# pin_conditiong.net
KiCad netlist of a schematic drawn in Altium Designer
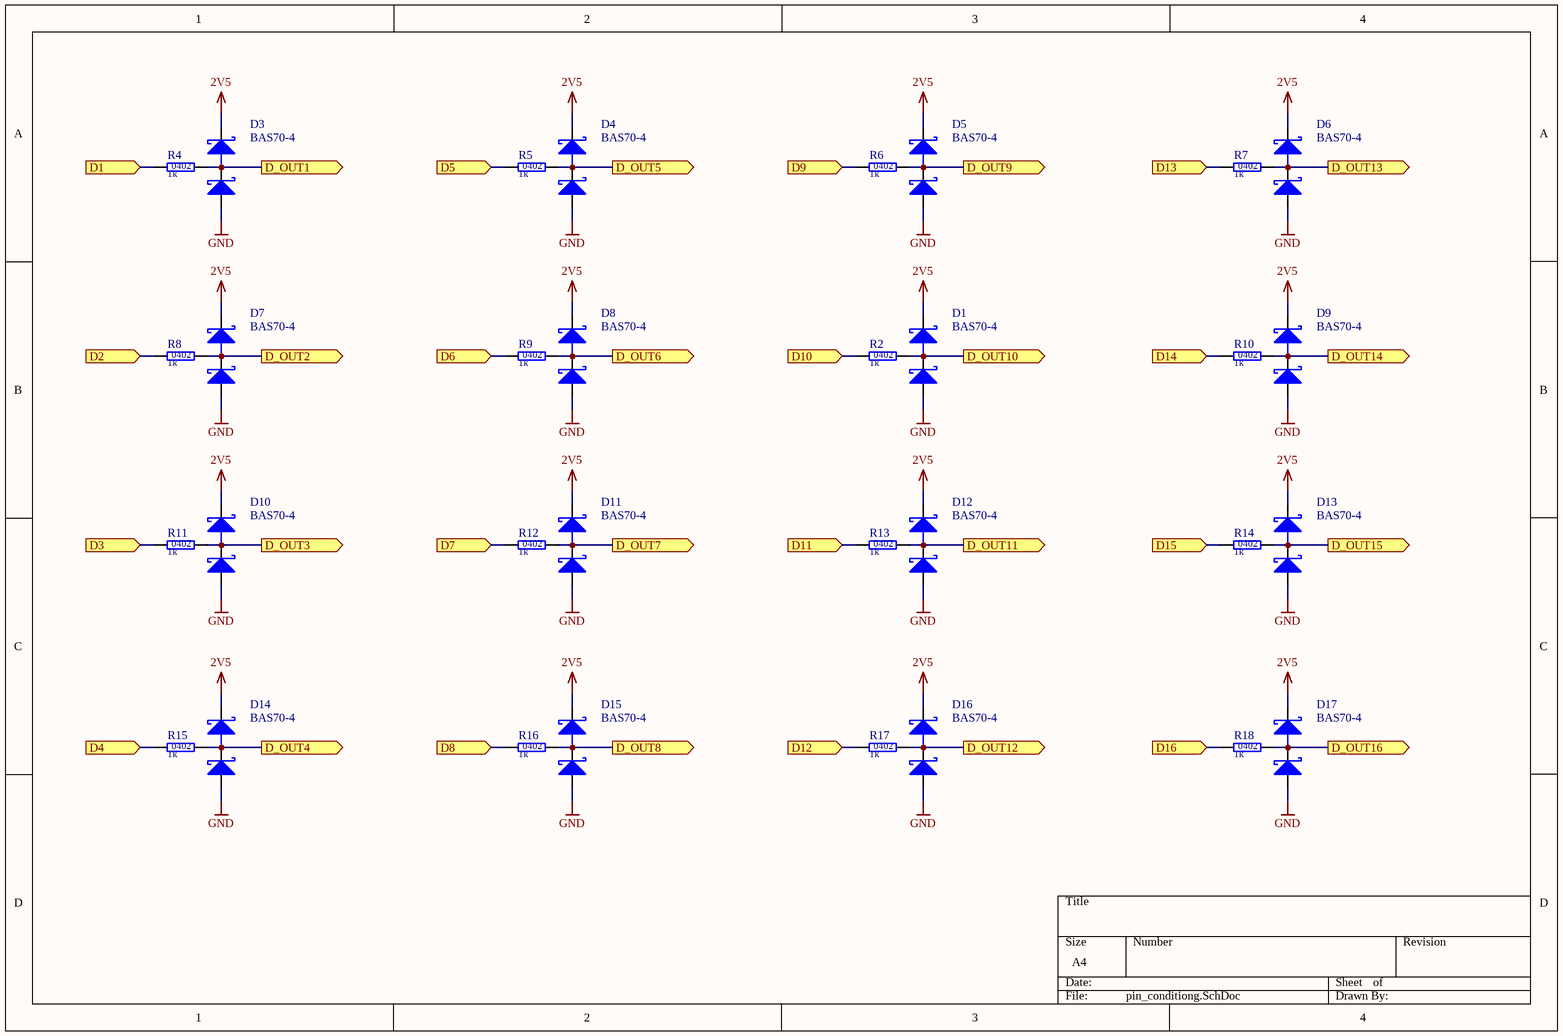
[diagram p0: pin_conditiong.SchDoc]

(export (version "E")
  (design (tool "Eeschema 10.0.6"))
  (components
    (comp (ref "D1")
      (value "BAS70-4")
      (footprint "BAS70-4")
      (description "Dioda: prostownicza Schottky; SMD; 70V; 70mA; 5ns; SOT23; 200mW")
      (libsource (lib "soldering_station") (part "BAS70-4"))
    )
    (comp (ref "D3")
      (value "BAS70-4")
      (footprint "BAS70-4")
      (description "Dioda: prostownicza Schottky; SMD; 70V; 70mA; 5ns; SOT23; 200mW")
      (libsource (lib "soldering_station") (part "BAS70-4"))
    )
    (comp (ref "D4")
      (value "BAS70-4")
      (footprint "BAS70-4")
      (description "Dioda: prostownicza Schottky; SMD; 70V; 70mA; 5ns; SOT23; 200mW")
      (libsource (lib "soldering_station") (part "BAS70-4"))
    )
    (comp (ref "D5")
      (value "BAS70-4")
      (footprint "BAS70-4")
      (description "Dioda: prostownicza Schottky; SMD; 70V; 70mA; 5ns; SOT23; 200mW")
      (libsource (lib "soldering_station") (part "BAS70-4"))
    )
    (comp (ref "D6")
      (value "BAS70-4")
      (footprint "BAS70-4")
      (description "Dioda: prostownicza Schottky; SMD; 70V; 70mA; 5ns; SOT23; 200mW")
      (libsource (lib "soldering_station") (part "BAS70-4"))
    )
    (comp (ref "D7")
      (value "BAS70-4")
      (footprint "BAS70-4")
      (description "Dioda: prostownicza Schottky; SMD; 70V; 70mA; 5ns; SOT23; 200mW")
      (libsource (lib "soldering_station") (part "BAS70-4"))
    )
    (comp (ref "D8")
      (value "BAS70-4")
      (footprint "BAS70-4")
      (description "Dioda: prostownicza Schottky; SMD; 70V; 70mA; 5ns; SOT23; 200mW")
      (libsource (lib "soldering_station") (part "BAS70-4"))
    )
    (comp (ref "D9")
      (value "BAS70-4")
      (footprint "BAS70-4")
      (description "Dioda: prostownicza Schottky; SMD; 70V; 70mA; 5ns; SOT23; 200mW")
      (libsource (lib "soldering_station") (part "BAS70-4"))
    )
    (comp (ref "D10")
      (value "BAS70-4")
      (footprint "BAS70-4")
      (description "Dioda: prostownicza Schottky; SMD; 70V; 70mA; 5ns; SOT23; 200mW")
      (libsource (lib "soldering_station") (part "BAS70-4"))
    )
    (comp (ref "D11")
      (value "BAS70-4")
      (footprint "BAS70-4")
      (description "Dioda: prostownicza Schottky; SMD; 70V; 70mA; 5ns; SOT23; 200mW")
      (libsource (lib "soldering_station") (part "BAS70-4"))
    )
    (comp (ref "D12")
      (value "BAS70-4")
      (footprint "BAS70-4")
      (description "Dioda: prostownicza Schottky; SMD; 70V; 70mA; 5ns; SOT23; 200mW")
      (libsource (lib "soldering_station") (part "BAS70-4"))
    )
    (comp (ref "D13")
      (value "BAS70-4")
      (footprint "BAS70-4")
      (description "Dioda: prostownicza Schottky; SMD; 70V; 70mA; 5ns; SOT23; 200mW")
      (libsource (lib "soldering_station") (part "BAS70-4"))
    )
    (comp (ref "D14")
      (value "BAS70-4")
      (footprint "BAS70-4")
      (description "Dioda: prostownicza Schottky; SMD; 70V; 70mA; 5ns; SOT23; 200mW")
      (libsource (lib "soldering_station") (part "BAS70-4"))
    )
    (comp (ref "D15")
      (value "BAS70-4")
      (footprint "BAS70-4")
      (description "Dioda: prostownicza Schottky; SMD; 70V; 70mA; 5ns; SOT23; 200mW")
      (libsource (lib "soldering_station") (part "BAS70-4"))
    )
    (comp (ref "D16")
      (value "BAS70-4")
      (footprint "BAS70-4")
      (description "Dioda: prostownicza Schottky; SMD; 70V; 70mA; 5ns; SOT23; 200mW")
      (libsource (lib "soldering_station") (part "BAS70-4"))
    )
    (comp (ref "D17")
      (value "BAS70-4")
      (footprint "BAS70-4")
      (description "Dioda: prostownicza Schottky; SMD; 70V; 70mA; 5ns; SOT23; 200mW")
      (libsource (lib "soldering_station") (part "BAS70-4"))
    )
    (comp (ref "R2")
      (value "1k")
      (footprint "R_0402_1005")
      (fields
        (field (name "SCH_FOOTPRINT") "0402")
        (field (name "PART NUMBER") "R_1k_0402_1")
        (field (name "VOLTAGE") "50V")
        (field (name "POWER") "63mW")
      )
      (libsource (lib "Library") (part "R"))
    )
    (comp (ref "R4")
      (value "1k")
      (footprint "R_0402_1005")
      (fields
        (field (name "SCH_FOOTPRINT") "0402")
        (field (name "PART NUMBER") "R_1k_0402_1")
        (field (name "VOLTAGE") "50V")
        (field (name "POWER") "63mW")
      )
      (libsource (lib "Library") (part "R"))
    )
    (comp (ref "R5")
      (value "1k")
      (footprint "R_0402_1005")
      (fields
        (field (name "SCH_FOOTPRINT") "0402")
        (field (name "PART NUMBER") "R_1k_0402_1")
        (field (name "VOLTAGE") "50V")
        (field (name "POWER") "63mW")
      )
      (libsource (lib "Library") (part "R"))
    )
    (comp (ref "R6")
      (value "1k")
      (footprint "R_0402_1005")
      (fields
        (field (name "SCH_FOOTPRINT") "0402")
        (field (name "PART NUMBER") "R_1k_0402_1")
        (field (name "VOLTAGE") "50V")
        (field (name "POWER") "63mW")
      )
      (libsource (lib "Library") (part "R"))
    )
    (comp (ref "R7")
      (value "1k")
      (footprint "R_0402_1005")
      (fields
        (field (name "SCH_FOOTPRINT") "0402")
        (field (name "PART NUMBER") "R_1k_0402_1")
        (field (name "VOLTAGE") "50V")
        (field (name "POWER") "63mW")
      )
      (libsource (lib "Library") (part "R"))
    )
    (comp (ref "R8")
      (value "1k")
      (footprint "R_0402_1005")
      (fields
        (field (name "SCH_FOOTPRINT") "0402")
        (field (name "PART NUMBER") "R_1k_0402_1")
        (field (name "VOLTAGE") "50V")
        (field (name "POWER") "63mW")
      )
      (libsource (lib "Library") (part "R"))
    )
    (comp (ref "R9")
      (value "1k")
      (footprint "R_0402_1005")
      (fields
        (field (name "SCH_FOOTPRINT") "0402")
        (field (name "PART NUMBER") "R_1k_0402_1")
        (field (name "VOLTAGE") "50V")
        (field (name "POWER") "63mW")
      )
      (libsource (lib "Library") (part "R"))
    )
    (comp (ref "R10")
      (value "1k")
      (footprint "R_0402_1005")
      (fields
        (field (name "SCH_FOOTPRINT") "0402")
        (field (name "PART NUMBER") "R_1k_0402_1")
        (field (name "VOLTAGE") "50V")
        (field (name "POWER") "63mW")
      )
      (libsource (lib "Library") (part "R"))
    )
    (comp (ref "R11")
      (value "1k")
      (footprint "R_0402_1005")
      (fields
        (field (name "SCH_FOOTPRINT") "0402")
        (field (name "PART NUMBER") "R_1k_0402_1")
        (field (name "VOLTAGE") "50V")
        (field (name "POWER") "63mW")
      )
      (libsource (lib "Library") (part "R"))
    )
    (comp (ref "R12")
      (value "1k")
      (footprint "R_0402_1005")
      (fields
        (field (name "SCH_FOOTPRINT") "0402")
        (field (name "PART NUMBER") "R_1k_0402_1")
        (field (name "VOLTAGE") "50V")
        (field (name "POWER") "63mW")
      )
      (libsource (lib "Library") (part "R"))
    )
    (comp (ref "R13")
      (value "1k")
      (footprint "R_0402_1005")
      (fields
        (field (name "SCH_FOOTPRINT") "0402")
        (field (name "PART NUMBER") "R_1k_0402_1")
        (field (name "VOLTAGE") "50V")
        (field (name "POWER") "63mW")
      )
      (libsource (lib "Library") (part "R"))
    )
    (comp (ref "R14")
      (value "1k")
      (footprint "R_0402_1005")
      (fields
        (field (name "SCH_FOOTPRINT") "0402")
        (field (name "PART NUMBER") "R_1k_0402_1")
        (field (name "VOLTAGE") "50V")
        (field (name "POWER") "63mW")
      )
      (libsource (lib "Library") (part "R"))
    )
    (comp (ref "R15")
      (value "1k")
      (footprint "R_0402_1005")
      (fields
        (field (name "SCH_FOOTPRINT") "0402")
        (field (name "PART NUMBER") "R_1k_0402_1")
        (field (name "VOLTAGE") "50V")
        (field (name "POWER") "63mW")
      )
      (libsource (lib "Library") (part "R"))
    )
    (comp (ref "R16")
      (value "1k")
      (footprint "R_0402_1005")
      (fields
        (field (name "SCH_FOOTPRINT") "0402")
        (field (name "PART NUMBER") "R_1k_0402_1")
        (field (name "VOLTAGE") "50V")
        (field (name "POWER") "63mW")
      )
      (libsource (lib "Library") (part "R"))
    )
    (comp (ref "R17")
      (value "1k")
      (footprint "R_0402_1005")
      (fields
        (field (name "SCH_FOOTPRINT") "0402")
        (field (name "PART NUMBER") "R_1k_0402_1")
        (field (name "VOLTAGE") "50V")
        (field (name "POWER") "63mW")
      )
      (libsource (lib "Library") (part "R"))
    )
    (comp (ref "R18")
      (value "1k")
      (footprint "R_0402_1005")
      (fields
        (field (name "SCH_FOOTPRINT") "0402")
        (field (name "PART NUMBER") "R_1k_0402_1")
        (field (name "VOLTAGE") "50V")
        (field (name "POWER") "63mW")
      )
      (libsource (lib "Library") (part "R"))
    )
  )
  (nets
    (net (code "1") (name "/D1") (class "Default")
      (node (ref "R4") (pin "1") (pinfunction "1_1") (pintype "passive"))
    )
    (net (code "2") (name "/D2") (class "Default")
      (node (ref "R8") (pin "1") (pinfunction "1_1") (pintype "passive"))
    )
    (net (code "3") (name "/D3") (class "Default")
      (node (ref "R11") (pin "1") (pinfunction "1_1") (pintype "passive"))
    )
    (net (code "4") (name "/D4") (class "Default")
      (node (ref "R15") (pin "1") (pinfunction "1_1") (pintype "passive"))
    )
    (net (code "5") (name "/D5") (class "Default")
      (node (ref "R5") (pin "1") (pinfunction "1_1") (pintype "passive"))
    )
    (net (code "6") (name "/D6") (class "Default")
      (node (ref "R9") (pin "1") (pinfunction "1_1") (pintype "passive"))
    )
    (net (code "7") (name "/D7") (class "Default")
      (node (ref "R12") (pin "1") (pinfunction "1_1") (pintype "passive"))
    )
    (net (code "8") (name "/D8") (class "Default")
      (node (ref "R16") (pin "1") (pinfunction "1_1") (pintype "passive"))
    )
    (net (code "9") (name "/D9") (class "Default")
      (node (ref "R6") (pin "1") (pinfunction "1_1") (pintype "passive"))
    )
    (net (code "10") (name "/D10") (class "Default")
      (node (ref "R2") (pin "1") (pinfunction "1_1") (pintype "passive"))
    )
    (net (code "11") (name "/D11") (class "Default")
      (node (ref "R13") (pin "1") (pinfunction "1_1") (pintype "passive"))
    )
    (net (code "12") (name "/D12") (class "Default")
      (node (ref "R17") (pin "1") (pinfunction "1_1") (pintype "passive"))
    )
    (net (code "13") (name "/D13") (class "Default")
      (node (ref "R7") (pin "1") (pinfunction "1_1") (pintype "passive"))
    )
    (net (code "14") (name "/D14") (class "Default")
      (node (ref "R10") (pin "1") (pinfunction "1_1") (pintype "passive"))
    )
    (net (code "15") (name "/D15") (class "Default")
      (node (ref "R14") (pin "1") (pinfunction "1_1") (pintype "passive"))
    )
    (net (code "16") (name "/D16") (class "Default")
      (node (ref "R18") (pin "1") (pinfunction "1_1") (pintype "passive"))
    )
    (net (code "17") (name "/D_OUT1") (class "Default")
      (node (ref "D3") (pin "3") (pinfunction "SIG_3") (pintype "passive"))
      (node (ref "R4") (pin "2") (pinfunction "2_2") (pintype "passive"))
    )
    (net (code "18") (name "/D_OUT2") (class "Default")
      (node (ref "D7") (pin "3") (pinfunction "SIG_3") (pintype "passive"))
      (node (ref "R8") (pin "2") (pinfunction "2_2") (pintype "passive"))
    )
    (net (code "19") (name "/D_OUT3") (class "Default")
      (node (ref "D10") (pin "3") (pinfunction "SIG_3") (pintype "passive"))
      (node (ref "R11") (pin "2") (pinfunction "2_2") (pintype "passive"))
    )
    (net (code "20") (name "/D_OUT4") (class "Default")
      (node (ref "D14") (pin "3") (pinfunction "SIG_3") (pintype "passive"))
      (node (ref "R15") (pin "2") (pinfunction "2_2") (pintype "passive"))
    )
    (net (code "21") (name "/D_OUT5") (class "Default")
      (node (ref "D4") (pin "3") (pinfunction "SIG_3") (pintype "passive"))
      (node (ref "R5") (pin "2") (pinfunction "2_2") (pintype "passive"))
    )
    (net (code "22") (name "/D_OUT6") (class "Default")
      (node (ref "D8") (pin "3") (pinfunction "SIG_3") (pintype "passive"))
      (node (ref "R9") (pin "2") (pinfunction "2_2") (pintype "passive"))
    )
    (net (code "23") (name "/D_OUT7") (class "Default")
      (node (ref "D11") (pin "3") (pinfunction "SIG_3") (pintype "passive"))
      (node (ref "R12") (pin "2") (pinfunction "2_2") (pintype "passive"))
    )
    (net (code "24") (name "/D_OUT8") (class "Default")
      (node (ref "D15") (pin "3") (pinfunction "SIG_3") (pintype "passive"))
      (node (ref "R16") (pin "2") (pinfunction "2_2") (pintype "passive"))
    )
    (net (code "25") (name "/D_OUT9") (class "Default")
      (node (ref "D5") (pin "3") (pinfunction "SIG_3") (pintype "passive"))
      (node (ref "R6") (pin "2") (pinfunction "2_2") (pintype "passive"))
    )
    (net (code "26") (name "/D_OUT10") (class "Default")
      (node (ref "D1") (pin "3") (pinfunction "SIG_3") (pintype "passive"))
      (node (ref "R2") (pin "2") (pinfunction "2_2") (pintype "passive"))
    )
    (net (code "27") (name "/D_OUT11") (class "Default")
      (node (ref "D12") (pin "3") (pinfunction "SIG_3") (pintype "passive"))
      (node (ref "R13") (pin "2") (pinfunction "2_2") (pintype "passive"))
    )
    (net (code "28") (name "/D_OUT12") (class "Default")
      (node (ref "D16") (pin "3") (pinfunction "SIG_3") (pintype "passive"))
      (node (ref "R17") (pin "2") (pinfunction "2_2") (pintype "passive"))
    )
    (net (code "29") (name "/D_OUT13") (class "Default")
      (node (ref "D6") (pin "3") (pinfunction "SIG_3") (pintype "passive"))
      (node (ref "R7") (pin "2") (pinfunction "2_2") (pintype "passive"))
    )
    (net (code "30") (name "/D_OUT14") (class "Default")
      (node (ref "D9") (pin "3") (pinfunction "SIG_3") (pintype "passive"))
      (node (ref "R10") (pin "2") (pinfunction "2_2") (pintype "passive"))
    )
    (net (code "31") (name "/D_OUT15") (class "Default")
      (node (ref "D13") (pin "3") (pinfunction "SIG_3") (pintype "passive"))
      (node (ref "R14") (pin "2") (pinfunction "2_2") (pintype "passive"))
    )
    (net (code "32") (name "/D_OUT16") (class "Default")
      (node (ref "D17") (pin "3") (pinfunction "SIG_3") (pintype "passive"))
      (node (ref "R18") (pin "2") (pinfunction "2_2") (pintype "passive"))
    )
    (net (code "33") (name "2V5") (class "Default")
      (node (ref "D1") (pin "2") (pinfunction "VCC_2") (pintype "passive"))
      (node (ref "D10") (pin "2") (pinfunction "VCC_2") (pintype "passive"))
      (node (ref "D11") (pin "2") (pinfunction "VCC_2") (pintype "passive"))
      (node (ref "D12") (pin "2") (pinfunction "VCC_2") (pintype "passive"))
      (node (ref "D13") (pin "2") (pinfunction "VCC_2") (pintype "passive"))
      (node (ref "D14") (pin "2") (pinfunction "VCC_2") (pintype "passive"))
      (node (ref "D15") (pin "2") (pinfunction "VCC_2") (pintype "passive"))
      (node (ref "D16") (pin "2") (pinfunction "VCC_2") (pintype "passive"))
      (node (ref "D17") (pin "2") (pinfunction "VCC_2") (pintype "passive"))
      (node (ref "D3") (pin "2") (pinfunction "VCC_2") (pintype "passive"))
      (node (ref "D4") (pin "2") (pinfunction "VCC_2") (pintype "passive"))
      (node (ref "D5") (pin "2") (pinfunction "VCC_2") (pintype "passive"))
      (node (ref "D6") (pin "2") (pinfunction "VCC_2") (pintype "passive"))
      (node (ref "D7") (pin "2") (pinfunction "VCC_2") (pintype "passive"))
      (node (ref "D8") (pin "2") (pinfunction "VCC_2") (pintype "passive"))
      (node (ref "D9") (pin "2") (pinfunction "VCC_2") (pintype "passive"))
    )
    (net (code "34") (name "GND") (class "Default")
      (node (ref "D1") (pin "1") (pinfunction "GND_1") (pintype "passive"))
      (node (ref "D10") (pin "1") (pinfunction "GND_1") (pintype "passive"))
      (node (ref "D11") (pin "1") (pinfunction "GND_1") (pintype "passive"))
      (node (ref "D12") (pin "1") (pinfunction "GND_1") (pintype "passive"))
      (node (ref "D13") (pin "1") (pinfunction "GND_1") (pintype "passive"))
      (node (ref "D14") (pin "1") (pinfunction "GND_1") (pintype "passive"))
      (node (ref "D15") (pin "1") (pinfunction "GND_1") (pintype "passive"))
      (node (ref "D16") (pin "1") (pinfunction "GND_1") (pintype "passive"))
      (node (ref "D17") (pin "1") (pinfunction "GND_1") (pintype "passive"))
      (node (ref "D3") (pin "1") (pinfunction "GND_1") (pintype "passive"))
      (node (ref "D4") (pin "1") (pinfunction "GND_1") (pintype "passive"))
      (node (ref "D5") (pin "1") (pinfunction "GND_1") (pintype "passive"))
      (node (ref "D6") (pin "1") (pinfunction "GND_1") (pintype "passive"))
      (node (ref "D7") (pin "1") (pinfunction "GND_1") (pintype "passive"))
      (node (ref "D8") (pin "1") (pinfunction "GND_1") (pintype "passive"))
      (node (ref "D9") (pin "1") (pinfunction "GND_1") (pintype "passive"))
    )
  )
)
